# LP.net
KiCad netlist of a schematic drawn in Altium Designer
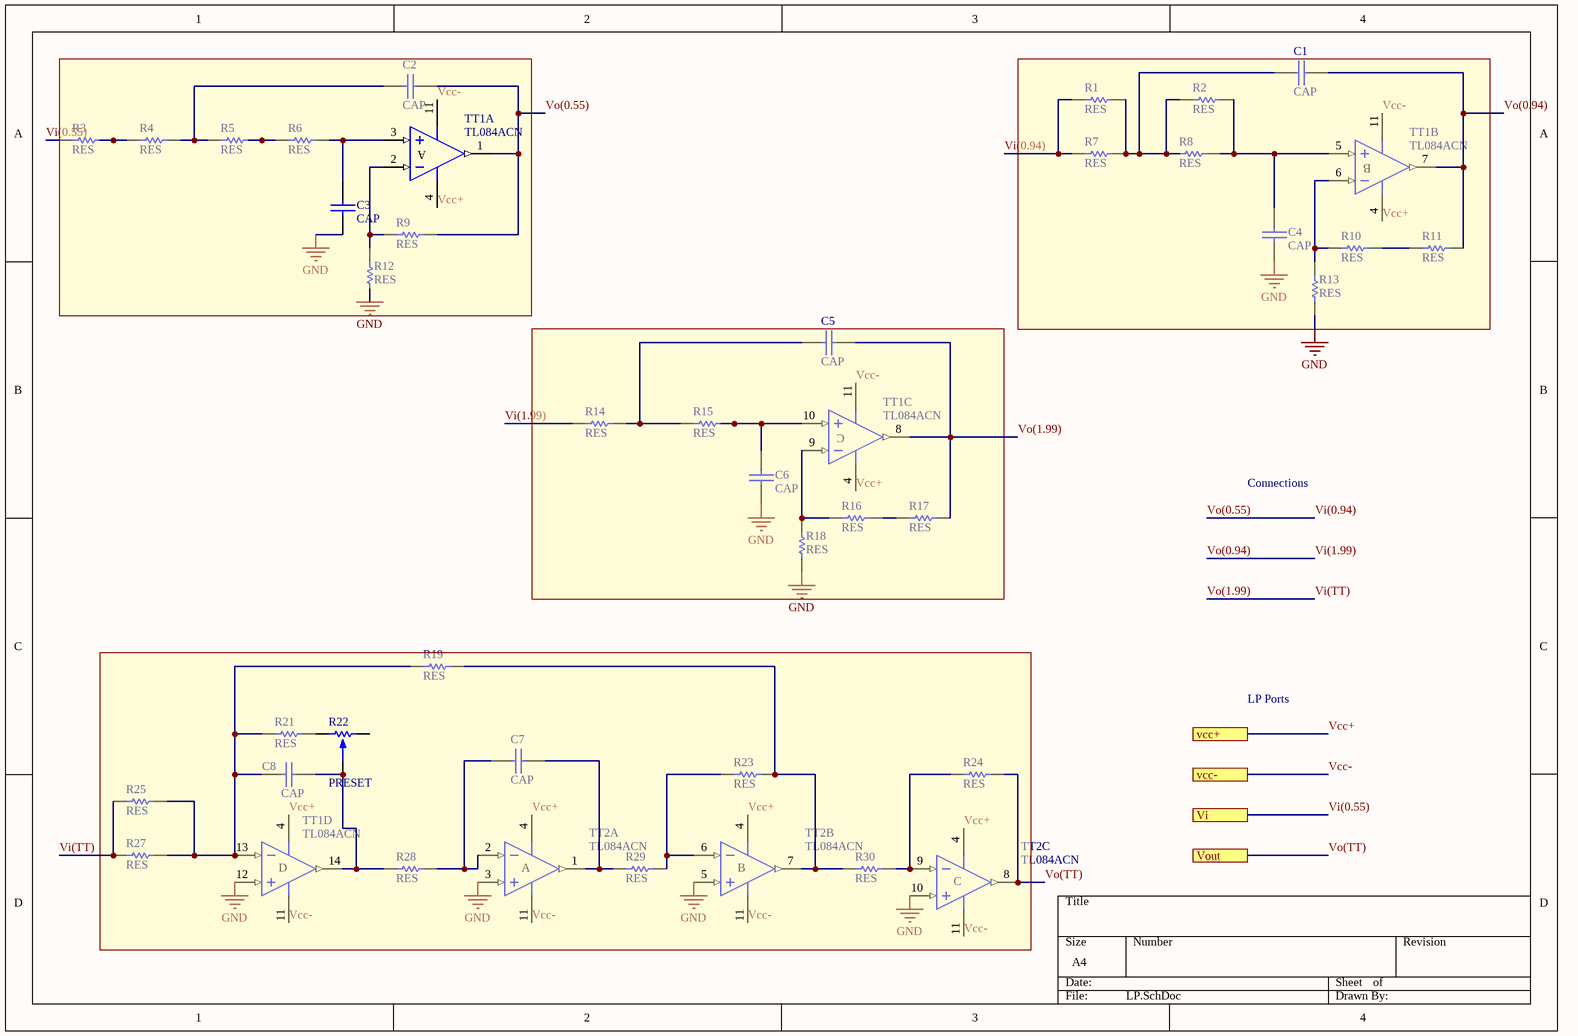
[diagram p0: LP.SchDoc]

(export (version "E")
  (design (tool "Eeschema 10.0.6"))
  (components
    (comp (ref "C1") (value "CAP") (footprint "0805") (libsource (lib "LIBEBAL") (part "CAP")))
    (comp (ref "C2") (value "CAP") (footprint "0805") (libsource (lib "LIBEBAL") (part "CAP")))
    (comp (ref "C3") (value "CAP") (footprint "0805") (libsource (lib "LIBEBAL") (part "CAP")))
    (comp (ref "C4") (value "CAP") (footprint "0805") (libsource (lib "LIBEBAL") (part "CAP")))
    (comp (ref "C5") (value "CAP") (footprint "0805") (libsource (lib "LIBEBAL") (part "CAP")))
    (comp (ref "C6") (value "CAP") (footprint "0805") (libsource (lib "LIBEBAL") (part "CAP")))
    (comp (ref "C7") (value "CAP") (footprint "0805") (libsource (lib "LIBEBAL") (part "CAP")))
    (comp (ref "C8") (value "CAP") (footprint "0805") (libsource (lib "LIBEBAL") (part "CAP")))
    (comp (ref "R1") (value "RES") (footprint "0805") (libsource (lib "LIBEBAL") (part "RES")))
    (comp (ref "R2") (value "RES") (footprint "0805") (libsource (lib "LIBEBAL") (part "RES")))
    (comp (ref "R3") (value "RES") (footprint "0805") (libsource (lib "LIBEBAL") (part "RES")))
    (comp (ref "R4") (value "RES") (footprint "0805") (libsource (lib "LIBEBAL") (part "RES")))
    (comp (ref "R5") (value "RES") (footprint "0805") (libsource (lib "LIBEBAL") (part "RES")))
    (comp (ref "R6") (value "RES") (footprint "0805") (libsource (lib "LIBEBAL") (part "RES")))
    (comp (ref "R7") (value "RES") (footprint "0805") (libsource (lib "LIBEBAL") (part "RES")))
    (comp (ref "R8") (value "RES") (footprint "0805") (libsource (lib "LIBEBAL") (part "RES")))
    (comp (ref "R9") (value "RES") (footprint "0805") (libsource (lib "LIBEBAL") (part "RES")))
    (comp (ref "R10") (value "RES") (footprint "0805") (libsource (lib "LIBEBAL") (part "RES")))
    (comp (ref "R11") (value "RES") (footprint "0805") (libsource (lib "LIBEBAL") (part "RES")))
    (comp (ref "R12") (value "RES") (footprint "0805") (libsource (lib "LIBEBAL") (part "RES")))
    (comp (ref "R13") (value "RES") (footprint "0805") (libsource (lib "LIBEBAL") (part "RES")))
    (comp (ref "R14") (value "RES") (footprint "0805") (libsource (lib "LIBEBAL") (part "RES")))
    (comp (ref "R15") (value "RES") (footprint "0805") (libsource (lib "LIBEBAL") (part "RES")))
    (comp (ref "R16") (value "RES") (footprint "0805") (libsource (lib "LIBEBAL") (part "RES")))
    (comp (ref "R17") (value "RES") (footprint "0805") (libsource (lib "LIBEBAL") (part "RES")))
    (comp (ref "R18") (value "RES") (footprint "0805") (libsource (lib "LIBEBAL") (part "RES")))
    (comp (ref "R19") (value "RES") (footprint "0805") (libsource (lib "LIBEBAL") (part "RES")))
    (comp (ref "R21") (value "RES") (footprint "0805") (libsource (lib "LIBEBAL") (part "RES")))
    (comp (ref "R22") (value "PRESET") (footprint "PRESET V") (libsource (lib "LIBEBAL") (part "PRESET")))
    (comp (ref "R23") (value "RES") (footprint "0805") (libsource (lib "LIBEBAL") (part "RES")))
    (comp (ref "R24") (value "RES") (footprint "0805") (libsource (lib "LIBEBAL") (part "RES")))
    (comp (ref "R25") (value "RES") (footprint "0805") (libsource (lib "LIBEBAL") (part "RES")))
    (comp (ref "R27") (value "RES") (footprint "0805") (libsource (lib "LIBEBAL") (part "RES")))
    (comp (ref "R28") (value "RES") (footprint "0805") (libsource (lib "LIBEBAL") (part "RES")))
    (comp (ref "R29") (value "RES") (footprint "0805") (libsource (lib "LIBEBAL") (part "RES")))
    (comp (ref "R30") (value "RES") (footprint "0805") (libsource (lib "LIBEBAL") (part "RES")))
    (comp (ref "TT1")
      (value "TL084ACN")
      (footprint "DIP14")
      (description "General-Purpose J-FET Quad Operational Amplifier")
      (fields (field (name "PUBLISHER") "Altium Limited"))
      (libsource (lib "TI Amplifiers and Linear Operational Amplifier General Purpose") (part "TL084ACN"))
    )
    (comp (ref "TT2")
      (value "TL084ACN")
      (footprint "DIP14")
      (description "General-Purpose J-FET Quad Operational Amplifier")
      (fields (field (name "PUBLISHER") "Altium Limited"))
      (libsource (lib "TI Amplifiers and Linear Operational Amplifier General Purpose") (part "TL084ACN"))
    )
  )
  (nets
    (net (code "1") (name "/Vcc+") (class "Default")
      (node (ref "TT1") (pin "4") (pinfunction "V+_4") (pintype "power_in"))
      (node (ref "TT2") (pin "4") (pinfunction "V+_4") (pintype "power_in"))
    )
    (net (code "2") (name "/Vcc-") (class "Default")
      (node (ref "TT1") (pin "11") (pinfunction "V-_11") (pintype "power_in"))
      (node (ref "TT2") (pin "11") (pinfunction "V-_11") (pintype "power_in"))
    )
    (net (code "3") (name "/Vi(0.55)") (class "Default")
      (node (ref "R3") (pin "1") (pinfunction "1_1") (pintype "passive"))
    )
    (net (code "4") (name "/Vi(0.94)") (class "Default")
      (node (ref "C2") (pin "2") (pinfunction "2_2") (pintype "passive"))
      (node (ref "R1") (pin "1") (pinfunction "1_1") (pintype "passive"))
      (node (ref "R7") (pin "1") (pinfunction "1_1") (pintype "passive"))
      (node (ref "R9") (pin "1") (pinfunction "1_1") (pintype "passive"))
      (node (ref "TT1") (pin "1") (pinfunction "OUT_1") (pintype "output"))
    )
    (net (code "5") (name "/Vi(1.99)") (class "Default")
      (node (ref "C1") (pin "2") (pinfunction "2_2") (pintype "passive"))
      (node (ref "R11") (pin "2") (pinfunction "2_2") (pintype "passive"))
      (node (ref "R14") (pin "1") (pinfunction "1_1") (pintype "passive"))
      (node (ref "TT1") (pin "7") (pinfunction "OUT_7") (pintype "output"))
    )
    (net (code "6") (name "/Vi(TT)") (class "Default")
      (node (ref "C5") (pin "2") (pinfunction "2_2") (pintype "passive"))
      (node (ref "R17") (pin "1") (pinfunction "1_1") (pintype "passive"))
      (node (ref "R25") (pin "1") (pinfunction "1_1") (pintype "passive"))
      (node (ref "R27") (pin "1") (pinfunction "1_1") (pintype "passive"))
      (node (ref "TT1") (pin "8") (pinfunction "OUT_8") (pintype "output"))
    )
    (net (code "7") (name "/Vo(TT)") (class "Default")
      (node (ref "R24") (pin "2") (pinfunction "2_2") (pintype "passive"))
      (node (ref "TT2") (pin "8") (pinfunction "OUT_8") (pintype "output"))
    )
    (net (code "8") (name "GND") (class "Default")
      (node (ref "C3") (pin "1") (pinfunction "1_1") (pintype "passive"))
      (node (ref "C4") (pin "1") (pinfunction "1_1") (pintype "passive"))
      (node (ref "C6") (pin "1") (pinfunction "1_1") (pintype "passive"))
      (node (ref "R12") (pin "1") (pinfunction "1_1") (pintype "passive"))
      (node (ref "R13") (pin "1") (pinfunction "1_1") (pintype "passive"))
      (node (ref "R18") (pin "1") (pinfunction "1_1") (pintype "passive"))
      (node (ref "TT1") (pin "12") (pinfunction "IN+_12") (pintype "input"))
      (node (ref "TT2") (pin "10") (pinfunction "IN+_10") (pintype "input"))
      (node (ref "TT2") (pin "3") (pinfunction "IN+_3") (pintype "input"))
      (node (ref "TT2") (pin "5") (pinfunction "IN+_5") (pintype "input"))
    )
    (net (code "9") (name "Net-(C1-Pad1)") (class "Default")
      (node (ref "C1") (pin "1") (pinfunction "1_1") (pintype "passive"))
      (node (ref "R1") (pin "2") (pinfunction "2_2") (pintype "passive"))
      (node (ref "R2") (pin "1") (pinfunction "1_1") (pintype "passive"))
      (node (ref "R7") (pin "2") (pinfunction "2_2") (pintype "passive"))
      (node (ref "R8") (pin "1") (pinfunction "1_1") (pintype "passive"))
    )
    (net (code "10") (name "Net-(C2-Pad1)") (class "Default")
      (node (ref "C2") (pin "1") (pinfunction "1_1") (pintype "passive"))
      (node (ref "R4") (pin "2") (pinfunction "2_2") (pintype "passive"))
      (node (ref "R5") (pin "1") (pinfunction "1_1") (pintype "passive"))
    )
    (net (code "11") (name "Net-(C5-Pad1)") (class "Default")
      (node (ref "C5") (pin "1") (pinfunction "1_1") (pintype "passive"))
      (node (ref "R14") (pin "2") (pinfunction "2_2") (pintype "passive"))
      (node (ref "R15") (pin "1") (pinfunction "1_1") (pintype "passive"))
    )
    (net (code "12") (name "Net-(R3-Pad2)") (class "Default")
      (node (ref "R3") (pin "2") (pinfunction "2_2") (pintype "passive"))
      (node (ref "R4") (pin "1") (pinfunction "1_1") (pintype "passive"))
    )
    (net (code "13") (name "Net-(R5-Pad2)") (class "Default")
      (node (ref "R5") (pin "2") (pinfunction "2_2") (pintype "passive"))
      (node (ref "R6") (pin "1") (pinfunction "1_1") (pintype "passive"))
    )
    (net (code "14") (name "Net-(R10-Pad1)") (class "Default")
      (node (ref "R10") (pin "1") (pinfunction "1_1") (pintype "passive"))
      (node (ref "R11") (pin "1") (pinfunction "1_1") (pintype "passive"))
    )
    (net (code "15") (name "Net-(R16-Pad1)") (class "Default")
      (node (ref "R16") (pin "1") (pinfunction "1_1") (pintype "passive"))
      (node (ref "R17") (pin "2") (pinfunction "2_2") (pintype "passive"))
    )
    (net (code "16") (name "Net-(R21-Pad2)") (class "Default")
      (node (ref "R21") (pin "2") (pinfunction "2_2") (pintype "passive"))
      (node (ref "R22") (pin "3") (pinfunction "3_3") (pintype "passive"))
    )
    (net (code "17") (name "Net-(TT1A-IN+)") (class "Default")
      (node (ref "C3") (pin "2") (pinfunction "2_2") (pintype "passive"))
      (node (ref "R6") (pin "2") (pinfunction "2_2") (pintype "passive"))
      (node (ref "TT1") (pin "3") (pinfunction "IN+_3") (pintype "input"))
    )
    (net (code "18") (name "Net-(TT1A-IN-)") (class "Default")
      (node (ref "R12") (pin "2") (pinfunction "2_2") (pintype "passive"))
      (node (ref "R9") (pin "2") (pinfunction "2_2") (pintype "passive"))
      (node (ref "TT1") (pin "2") (pinfunction "IN-_2") (pintype "input"))
    )
    (net (code "19") (name "Net-(TT1B-IN+)") (class "Default")
      (node (ref "C4") (pin "2") (pinfunction "2_2") (pintype "passive"))
      (node (ref "R2") (pin "2") (pinfunction "2_2") (pintype "passive"))
      (node (ref "R8") (pin "2") (pinfunction "2_2") (pintype "passive"))
      (node (ref "TT1") (pin "5") (pinfunction "IN+_5") (pintype "input"))
    )
    (net (code "20") (name "Net-(TT1B-IN-)") (class "Default")
      (node (ref "R10") (pin "2") (pinfunction "2_2") (pintype "passive"))
      (node (ref "R13") (pin "2") (pinfunction "2_2") (pintype "passive"))
      (node (ref "TT1") (pin "6") (pinfunction "IN-_6") (pintype "input"))
    )
    (net (code "21") (name "Net-(TT1C-IN+)") (class "Default")
      (node (ref "C6") (pin "2") (pinfunction "2_2") (pintype "passive"))
      (node (ref "R15") (pin "2") (pinfunction "2_2") (pintype "passive"))
      (node (ref "TT1") (pin "10") (pinfunction "IN+_10") (pintype "input"))
    )
    (net (code "22") (name "Net-(TT1C-IN-)") (class "Default")
      (node (ref "R16") (pin "2") (pinfunction "2_2") (pintype "passive"))
      (node (ref "R18") (pin "2") (pinfunction "2_2") (pintype "passive"))
      (node (ref "TT1") (pin "9") (pinfunction "IN-_9") (pintype "input"))
    )
    (net (code "23") (name "Net-(TT1D-IN-)") (class "Default")
      (node (ref "C8") (pin "1") (pinfunction "1_1") (pintype "passive"))
      (node (ref "R19") (pin "1") (pinfunction "1_1") (pintype "passive"))
      (node (ref "R21") (pin "1") (pinfunction "1_1") (pintype "passive"))
      (node (ref "R25") (pin "2") (pinfunction "2_2") (pintype "passive"))
      (node (ref "R27") (pin "2") (pinfunction "2_2") (pintype "passive"))
      (node (ref "TT1") (pin "13") (pinfunction "IN-_13") (pintype "input"))
    )
    (net (code "24") (name "Net-(TT1D-OUT)") (class "Default")
      (node (ref "C8") (pin "2") (pinfunction "2_2") (pintype "passive"))
      (node (ref "R22") (pin "2") (pinfunction "2_2") (pintype "passive"))
      (node (ref "R28") (pin "1") (pinfunction "1_1") (pintype "passive"))
      (node (ref "TT1") (pin "14") (pinfunction "OUT_14") (pintype "output"))
    )
    (net (code "25") (name "Net-(TT2A-IN-)") (class "Default")
      (node (ref "C7") (pin "1") (pinfunction "1_1") (pintype "passive"))
      (node (ref "R28") (pin "2") (pinfunction "2_2") (pintype "passive"))
      (node (ref "TT2") (pin "2") (pinfunction "IN-_2") (pintype "input"))
    )
    (net (code "26") (name "Net-(TT2A-OUT)") (class "Default")
      (node (ref "C7") (pin "2") (pinfunction "2_2") (pintype "passive"))
      (node (ref "R29") (pin "1") (pinfunction "1_1") (pintype "passive"))
      (node (ref "TT2") (pin "1") (pinfunction "OUT_1") (pintype "output"))
    )
    (net (code "27") (name "Net-(TT2B-IN-)") (class "Default")
      (node (ref "R23") (pin "1") (pinfunction "1_1") (pintype "passive"))
      (node (ref "R29") (pin "2") (pinfunction "2_2") (pintype "passive"))
      (node (ref "TT2") (pin "6") (pinfunction "IN-_6") (pintype "input"))
    )
    (net (code "28") (name "Net-(TT2B-OUT)") (class "Default")
      (node (ref "R19") (pin "2") (pinfunction "2_2") (pintype "passive"))
      (node (ref "R23") (pin "2") (pinfunction "2_2") (pintype "passive"))
      (node (ref "R30") (pin "1") (pinfunction "1_1") (pintype "passive"))
      (node (ref "TT2") (pin "7") (pinfunction "OUT_7") (pintype "output"))
    )
    (net (code "29") (name "Net-(TT2C-IN-)") (class "Default")
      (node (ref "R24") (pin "1") (pinfunction "1_1") (pintype "passive"))
      (node (ref "R30") (pin "2") (pinfunction "2_2") (pintype "passive"))
      (node (ref "TT2") (pin "9") (pinfunction "IN-_9") (pintype "input"))
    )
    (net (code "30") (name "unconnected-(R22-Pad1)") (class "Default")
      (node (ref "R22") (pin "1") (pinfunction "1_1") (pintype "passive"))
    )
  )
)
